# SIM808.net
KiCad netlist of a schematic drawn in Altium Designer
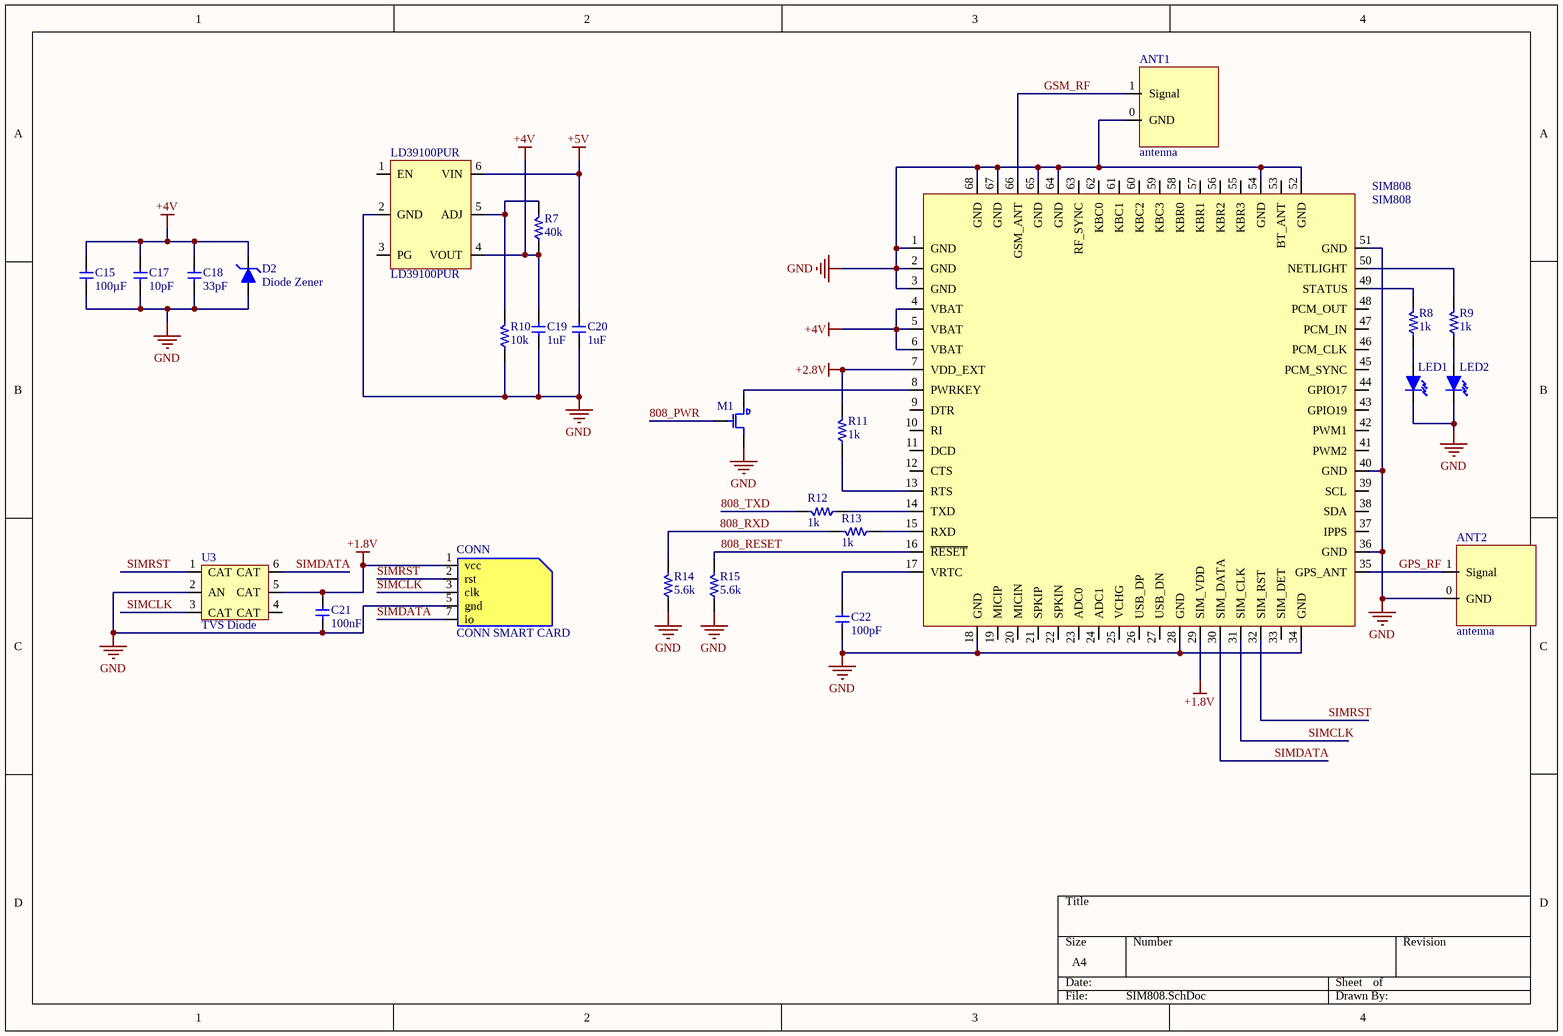
[diagram p0: SIM808.SchDoc]

(export (version "E")
  (design (tool "Eeschema 10.0.6"))
  (components
    (comp (ref "ANT1")
      (value "antenna")
      (footprint "uFL")
      (description "uFL SMT Antenna Connector")
      (fields (field (name "MFR") "adafruit"))
      (libsource (lib "uFLAntenna") (part "antenna"))
    )
    (comp (ref "ANT2")
      (value "antenna")
      (footprint "uFL")
      (description "uFL SMT Antenna Connector")
      (fields (field (name "MFR") "adafruit"))
      (libsource (lib "uFLAntenna") (part "antenna"))
    )
    (comp (ref "C15")
      (value "Cap Cer 100uF")
      (footprint "Cap 1210")
      (description "CAP CER 100UF 10V X5R 1210")
      (fields
        (field (name "MANUFACTURER") "Taiyo Yuden")
        (field (name "MANUFACTURER PART NUMBER") "LMK325ABJ107MM-P")
        (field (name "CAPACITANCE") "100µF")
      )
      (libsource (lib "SIM808") (part "LMK325ABJ107MM-P"))
    )
    (comp (ref "C17")
      (value "10pF")
      (footprint "0805")
      (description "Generic capacitor")
      (fields (field (name "Comment") "Generic Capacitor"))
      (libsource (lib "PowerCircuit") (part "Capacitor"))
    )
    (comp (ref "C18")
      (value "33pF")
      (footprint "0805")
      (description "Generic capacitor")
      (fields (field (name "Comment") "Generic Capacitor"))
      (libsource (lib "PowerCircuit") (part "Capacitor"))
    )
    (comp (ref "C19")
      (value "1uF")
      (footprint "0805")
      (description "Generic capacitor")
      (fields (field (name "Comment") "Generic Capacitor"))
      (libsource (lib "PowerCircuit") (part "Capacitor"))
    )
    (comp (ref "C20")
      (value "1uF")
      (footprint "0805")
      (description "Generic capacitor")
      (fields (field (name "Comment") "Generic Capacitor"))
      (libsource (lib "PowerCircuit") (part "Capacitor"))
    )
    (comp (ref "C21")
      (value "100nF")
      (footprint "0805")
      (description "Generic capacitor")
      (fields (field (name "Comment") "Generic Capacitor"))
      (libsource (lib "PowerCircuit") (part "Capacitor"))
    )
    (comp (ref "C22")
      (value "100pF")
      (footprint "0805")
      (description "Generic capacitor")
      (fields (field (name "Comment") "Generic Capacitor"))
      (libsource (lib "PowerCircuit") (part "Capacitor"))
    )
    (comp (ref "CONN")
      (value "CONN SMART CARD")
      (footprint "CONN SMART CARD")
      (fields
        (field (name "MANUFACTURER") "Wurth Electronics Inc")
        (field (name "MANUFACTURER PART NUMBER") "693022010811")
      )
      (libsource (lib "SIM808") (part "CONN SMART CARD"))
    )
    (comp (ref "D2")
      (value "Diode Zener")
      (footprint "Diode Zener")
      (description "DIODE ZENER 5.1V 500MW SOD123")
      (fields
        (field (name "MANUFACTURER") "ON Semiconductor")
        (field (name "MANUFACTURER PART NUMBER") "MMSZ5231BT1G")
      )
      (libsource (lib "SIM808") (part "MMSZ5231BT1G"))
    )
    (comp (ref "LD39100PUR")
      (value "LD39100PUR")
      (footprint "LD39100PUR")
      (description "Adjustable linear voltage regulator")
      (fields (field (name "MFR") "ST"))
      (libsource (lib "SIM808") (part "LD39100PUR"))
    )
    (comp (ref "LED1")
      (value "Led Red")
      (footprint "0805 LED")
      (description "LED RED CLEAR 0805 SMD")
      (fields
        (field (name "MANUFACTURER") "Lite-On Inc.")
        (field (name "MANUFACTURER PART NUMBER") "LTST-C171EKT")
      )
      (libsource (lib "SIM808") (part "LTST-C171EKT"))
    )
    (comp (ref "LED2")
      (value "Led Green")
      (footprint "0805 LED")
      (description "LED GREEN CLEAR 0805 SMD")
      (fields
        (field (name "MANUFACTURER") "Lite-On Inc.")
        (field (name "MANUFACTURER PART NUMBER") "LTST-C170GKT")
      )
      (libsource (lib "SIM808") (part "LTST-C170GKT"))
    )
    (comp (ref "M1")
      (value "N-CH Mosfet Switch")
      (footprint "SOT32-3")
      (description "MOSFET N-CH 20V 1.05A SOT23")
      (fields
        (field (name "MANUFACTURER") "NXP USA Inc.")
        (field (name "MANUFACTURER PART NUMBER") "BSH105,215")
      )
      (libsource (lib "SIM808") (part "BSH105,215"))
    )
    (comp (ref "R7")
      (value "40k")
      (footprint "0805")
      (description "Generic Resistor")
      (fields (field (name "Comment") "Resistor"))
      (libsource (lib "PowerCircuit") (part "Resistor"))
    )
    (comp (ref "R8")
      (value "1k")
      (footprint "0805")
      (description "Generic Resistor")
      (fields (field (name "Comment") "Resistor"))
      (libsource (lib "PowerCircuit") (part "Resistor"))
    )
    (comp (ref "R9")
      (value "1k")
      (footprint "0805")
      (description "Generic Resistor")
      (fields (field (name "Comment") "Resistor"))
      (libsource (lib "PowerCircuit") (part "Resistor"))
    )
    (comp (ref "R10")
      (value "10k")
      (footprint "0805")
      (description "Generic Resistor")
      (fields (field (name "Comment") "Resistor"))
      (libsource (lib "PowerCircuit") (part "Resistor"))
    )
    (comp (ref "R11")
      (value "1k")
      (footprint "0805")
      (description "Generic Resistor")
      (fields (field (name "Comment") "Resistor"))
      (libsource (lib "PowerCircuit") (part "Resistor"))
    )
    (comp (ref "R12")
      (value "1k")
      (footprint "0805")
      (description "Generic Resistor")
      (fields (field (name "Comment") "Resistor"))
      (libsource (lib "PowerCircuit") (part "Resistor"))
    )
    (comp (ref "R13")
      (value "1k")
      (footprint "0805")
      (description "Generic Resistor")
      (fields (field (name "Comment") "Resistor"))
      (libsource (lib "PowerCircuit") (part "Resistor"))
    )
    (comp (ref "R14")
      (value "5.6k")
      (footprint "0805")
      (description "Generic Resistor")
      (fields (field (name "Comment") "Resistor"))
      (libsource (lib "PowerCircuit") (part "Resistor"))
    )
    (comp (ref "R15")
      (value "5.6k")
      (footprint "0805")
      (description "Generic Resistor")
      (fields (field (name "Comment") "Resistor"))
      (libsource (lib "PowerCircuit") (part "Resistor"))
    )
    (comp (ref "SIM808")
      (value "SIM808")
      (footprint "SIM808")
      (description "SIM808 GSM + GPRS + GPS Cellular Module")
      (fields (field (name "MFR") "SimCom"))
      (libsource (lib "SIM808") (part "SIM808"))
    )
    (comp (ref "U3")
      (value "TVS Diode")
      (footprint "SMF05CT2G")
      (description "TVS DIODE 5VWM 12.5VC SOT363")
      (fields
        (field (name "MANUFACTURER") "ON Semiconductor")
        (field (name "MANUFACTURER PART NUMBER") "SMF05CT2G")
      )
      (libsource (lib "SIM808") (part "SMF05CT2G"))
    )
  )
  (nets
    (net (code "1") (name "+1.8V") (class "Default")
      (node (ref "C21") (pin "1") (pinfunction "1_1") (pintype "passive"))
      (node (ref "CONN") (pin "1") (pinfunction "vcc_1") (pintype "passive"))
      (node (ref "SIM808") (pin "29") (pinfunction "SIM_VDD_29") (pintype "passive"))
      (node (ref "U3") (pin "5") (pinfunction "CAT_5") (pintype "passive"))
    )
    (net (code "2") (name "+2.8V") (class "Default")
      (node (ref "R11") (pin "2") (pinfunction "2_2") (pintype "passive"))
      (node (ref "SIM808") (pin "7") (pinfunction "VDD_EXT_7") (pintype "passive"))
    )
    (net (code "3") (name "+4V") (class "Default")
      (node (ref "C15") (pin "1") (pinfunction "1_1") (pintype "passive"))
      (node (ref "C17") (pin "1") (pinfunction "1_1") (pintype "passive"))
      (node (ref "C18") (pin "1") (pinfunction "1_1") (pintype "passive"))
      (node (ref "C19") (pin "2") (pinfunction "2_2") (pintype "passive"))
      (node (ref "D2") (pin "1") (pinfunction "1_1") (pintype "passive"))
      (node (ref "LD39100PUR") (pin "4") (pinfunction "VOUT_4") (pintype "passive"))
      (node (ref "R7") (pin "1") (pinfunction "1_1") (pintype "passive"))
      (node (ref "SIM808") (pin "4") (pinfunction "VBAT_4") (pintype "passive"))
      (node (ref "SIM808") (pin "5") (pinfunction "VBAT_5") (pintype "passive"))
      (node (ref "SIM808") (pin "6") (pinfunction "VBAT_6") (pintype "passive"))
    )
    (net (code "4") (name "+5V") (class "Default")
      (node (ref "C20") (pin "1") (pinfunction "1_1") (pintype "passive"))
      (node (ref "LD39100PUR") (pin "6") (pinfunction "VIN_6") (pintype "passive"))
    )
    (net (code "5") (name "/808_PWR") (class "Default")
      (node (ref "M1") (pin "1") (pinfunction "G_1") (pintype "passive"))
    )
    (net (code "6") (name "/808_RESET") (class "Default")
      (node (ref "R15") (pin "2") (pinfunction "2_2") (pintype "passive"))
      (node (ref "SIM808") (pin "16") (pinfunction "~{RESET}_16") (pintype "passive"))
    )
    (net (code "7") (name "/808_RXD") (class "Default")
      (node (ref "R13") (pin "2") (pinfunction "2_2") (pintype "passive"))
      (node (ref "R14") (pin "2") (pinfunction "2_2") (pintype "passive"))
    )
    (net (code "8") (name "/808_TXD") (class "Default")
      (node (ref "R12") (pin "2") (pinfunction "2_2") (pintype "passive"))
    )
    (net (code "9") (name "/GPS_RF") (class "Default")
      (node (ref "ANT2") (pin "1") (pinfunction "Signal_1") (pintype "passive"))
      (node (ref "SIM808") (pin "35") (pinfunction "GPS_ANT_35") (pintype "passive"))
    )
    (net (code "10") (name "/GSM_RF") (class "Default")
      (node (ref "ANT1") (pin "1") (pinfunction "Signal_1") (pintype "passive"))
      (node (ref "SIM808") (pin "66") (pinfunction "GSM_ANT_66") (pintype "passive"))
    )
    (net (code "11") (name "/SIMCLK") (class "Default")
      (node (ref "CONN") (pin "3") (pinfunction "clk_3") (pintype "passive"))
      (node (ref "SIM808") (pin "31") (pinfunction "SIM_CLK_31") (pintype "passive"))
      (node (ref "U3") (pin "3") (pinfunction "CAT_3") (pintype "passive"))
    )
    (net (code "12") (name "/SIMDATA") (class "Default")
      (node (ref "CONN") (pin "7") (pinfunction "io_7") (pintype "passive"))
      (node (ref "SIM808") (pin "30") (pinfunction "SIM_DATA_30") (pintype "passive"))
      (node (ref "U3") (pin "6") (pinfunction "CAT_6") (pintype "passive"))
    )
    (net (code "13") (name "/SIMRST") (class "Default")
      (node (ref "CONN") (pin "2") (pinfunction "rst_2") (pintype "passive"))
      (node (ref "SIM808") (pin "32") (pinfunction "SIM_RST_32") (pintype "passive"))
      (node (ref "U3") (pin "1") (pinfunction "CAT_1") (pintype "passive"))
    )
    (net (code "14") (name "GND") (class "Default")
      (node (ref "ANT1") (pin "0") (pinfunction "GND_0") (pintype "passive"))
      (node (ref "ANT2") (pin "0") (pinfunction "GND_0") (pintype "passive"))
      (node (ref "C15") (pin "2") (pinfunction "2_2") (pintype "passive"))
      (node (ref "C17") (pin "2") (pinfunction "2_2") (pintype "passive"))
      (node (ref "C18") (pin "2") (pinfunction "2_2") (pintype "passive"))
      (node (ref "C19") (pin "1") (pinfunction "1_1") (pintype "passive"))
      (node (ref "C20") (pin "2") (pinfunction "2_2") (pintype "passive"))
      (node (ref "C21") (pin "2") (pinfunction "2_2") (pintype "passive"))
      (node (ref "C22") (pin "2") (pinfunction "2_2") (pintype "passive"))
      (node (ref "CONN") (pin "5") (pinfunction "gnd_5") (pintype "passive"))
      (node (ref "D2") (pin "2") (pinfunction "2_2") (pintype "passive"))
      (node (ref "LD39100PUR") (pin "2") (pinfunction "GND_2") (pintype "passive"))
      (node (ref "LED1") (pin "1") (pinfunction "1_1") (pintype "passive"))
      (node (ref "LED2") (pin "1") (pinfunction "1_1") (pintype "passive"))
      (node (ref "M1") (pin "2") (pinfunction "S_2") (pintype "passive"))
      (node (ref "R10") (pin "1") (pinfunction "1_1") (pintype "passive"))
      (node (ref "R14") (pin "1") (pinfunction "1_1") (pintype "passive"))
      (node (ref "R15") (pin "1") (pinfunction "1_1") (pintype "passive"))
      (node (ref "SIM808") (pin "1") (pinfunction "GND_1") (pintype "passive"))
      (node (ref "SIM808") (pin "18") (pinfunction "GND_18") (pintype "passive"))
      (node (ref "SIM808") (pin "2") (pinfunction "GND_2") (pintype "passive"))
      (node (ref "SIM808") (pin "28") (pinfunction "GND_28") (pintype "passive"))
      (node (ref "SIM808") (pin "3") (pinfunction "GND_3") (pintype "passive"))
      (node (ref "SIM808") (pin "34") (pinfunction "GND_34") (pintype "passive"))
      (node (ref "SIM808") (pin "36") (pinfunction "GND_36") (pintype "passive"))
      (node (ref "SIM808") (pin "40") (pinfunction "GND_40") (pintype "passive"))
      (node (ref "SIM808") (pin "51") (pinfunction "GND_51") (pintype "passive"))
      (node (ref "SIM808") (pin "52") (pinfunction "GND_52") (pintype "passive"))
      (node (ref "SIM808") (pin "54") (pinfunction "GND_54") (pintype "passive"))
      (node (ref "SIM808") (pin "64") (pinfunction "GND_64") (pintype "passive"))
      (node (ref "SIM808") (pin "65") (pinfunction "GND_65") (pintype "passive"))
      (node (ref "SIM808") (pin "67") (pinfunction "GND_67") (pintype "passive"))
      (node (ref "SIM808") (pin "68") (pinfunction "GND_68") (pintype "passive"))
      (node (ref "U3") (pin "2") (pinfunction "AN_2") (pintype "passive"))
    )
    (net (code "15") (name "Net-(LD39100PUR-ADJ)") (class "Default")
      (node (ref "LD39100PUR") (pin "5") (pinfunction "ADJ_5") (pintype "passive"))
      (node (ref "R10") (pin "2") (pinfunction "2_2") (pintype "passive"))
      (node (ref "R7") (pin "2") (pinfunction "2_2") (pintype "passive"))
    )
    (net (code "16") (name "Net-(LED1-Pad2)") (class "Default")
      (node (ref "LED1") (pin "2") (pinfunction "2_2") (pintype "passive"))
      (node (ref "R8") (pin "1") (pinfunction "1_1") (pintype "passive"))
    )
    (net (code "17") (name "Net-(LED2-Pad2)") (class "Default")
      (node (ref "LED2") (pin "2") (pinfunction "2_2") (pintype "passive"))
      (node (ref "R9") (pin "1") (pinfunction "1_1") (pintype "passive"))
    )
    (net (code "18") (name "Net-(M1-D)") (class "Default")
      (node (ref "M1") (pin "3") (pinfunction "D_3") (pintype "passive"))
      (node (ref "SIM808") (pin "8") (pinfunction "PWRKEY_8") (pintype "passive"))
    )
    (net (code "19") (name "Net-(SIM808-NETLIGHT)") (class "Default")
      (node (ref "R9") (pin "2") (pinfunction "2_2") (pintype "passive"))
      (node (ref "SIM808") (pin "50") (pinfunction "NETLIGHT_50") (pintype "passive"))
    )
    (net (code "20") (name "Net-(SIM808-RTS)") (class "Default")
      (node (ref "R11") (pin "1") (pinfunction "1_1") (pintype "passive"))
      (node (ref "SIM808") (pin "13") (pinfunction "RTS_13") (pintype "passive"))
    )
    (net (code "21") (name "Net-(SIM808-RXD)") (class "Default")
      (node (ref "R13") (pin "1") (pinfunction "1_1") (pintype "passive"))
      (node (ref "SIM808") (pin "15") (pinfunction "RXD_15") (pintype "passive"))
    )
    (net (code "22") (name "Net-(SIM808-STATUS)") (class "Default")
      (node (ref "R8") (pin "2") (pinfunction "2_2") (pintype "passive"))
      (node (ref "SIM808") (pin "49") (pinfunction "STATUS_49") (pintype "passive"))
    )
    (net (code "23") (name "Net-(SIM808-TXD)") (class "Default")
      (node (ref "R12") (pin "1") (pinfunction "1_1") (pintype "passive"))
      (node (ref "SIM808") (pin "14") (pinfunction "TXD_14") (pintype "passive"))
    )
    (net (code "24") (name "Net-(SIM808-VRTC)") (class "Default")
      (node (ref "C22") (pin "1") (pinfunction "1_1") (pintype "passive"))
      (node (ref "SIM808") (pin "17") (pinfunction "VRTC_17") (pintype "passive"))
    )
    (net (code "25") (name "unconnected-(LD39100PUR-EN-Pad1)") (class "Default")
      (node (ref "LD39100PUR") (pin "1") (pinfunction "EN_1") (pintype "passive"))
    )
    (net (code "26") (name "unconnected-(LD39100PUR-PG-Pad3)") (class "Default")
      (node (ref "LD39100PUR") (pin "3") (pinfunction "PG_3") (pintype "passive"))
    )
    (net (code "27") (name "unconnected-(SIM808-ADC0-Pad23)") (class "Default")
      (node (ref "SIM808") (pin "23") (pinfunction "ADC0_23") (pintype "passive"))
    )
    (net (code "28") (name "unconnected-(SIM808-ADC1-Pad24)") (class "Default")
      (node (ref "SIM808") (pin "24") (pinfunction "ADC1_24") (pintype "passive"))
    )
    (net (code "29") (name "unconnected-(SIM808-BT_ANT-Pad53)") (class "Default")
      (node (ref "SIM808") (pin "53") (pinfunction "BT_ANT_53") (pintype "passive"))
    )
    (net (code "30") (name "unconnected-(SIM808-CTS-Pad12)") (class "Default")
      (node (ref "SIM808") (pin "12") (pinfunction "CTS_12") (pintype "passive"))
    )
    (net (code "31") (name "unconnected-(SIM808-DCD-Pad11)") (class "Default")
      (node (ref "SIM808") (pin "11") (pinfunction "DCD_11") (pintype "passive"))
    )
    (net (code "32") (name "unconnected-(SIM808-DTR-Pad9)") (class "Default")
      (node (ref "SIM808") (pin "9") (pinfunction "DTR_9") (pintype "passive"))
    )
    (net (code "33") (name "unconnected-(SIM808-GPIO17-Pad44)") (class "Default")
      (node (ref "SIM808") (pin "44") (pinfunction "GPIO17_44") (pintype "passive"))
    )
    (net (code "34") (name "unconnected-(SIM808-GPIO19-Pad43)") (class "Default")
      (node (ref "SIM808") (pin "43") (pinfunction "GPIO19_43") (pintype "passive"))
    )
    (net (code "35") (name "unconnected-(SIM808-IPPS-Pad37)") (class "Default")
      (node (ref "SIM808") (pin "37") (pinfunction "IPPS_37") (pintype "passive"))
    )
    (net (code "36") (name "unconnected-(SIM808-KBC0-Pad62)") (class "Default")
      (node (ref "SIM808") (pin "62") (pinfunction "KBC0_62") (pintype "passive"))
    )
    (net (code "37") (name "unconnected-(SIM808-KBC1-Pad61)") (class "Default")
      (node (ref "SIM808") (pin "61") (pinfunction "KBC1_61") (pintype "passive"))
    )
    (net (code "38") (name "unconnected-(SIM808-KBC2-Pad60)") (class "Default")
      (node (ref "SIM808") (pin "60") (pinfunction "KBC2_60") (pintype "passive"))
    )
    (net (code "39") (name "unconnected-(SIM808-KBC3-Pad59)") (class "Default")
      (node (ref "SIM808") (pin "59") (pinfunction "KBC3_59") (pintype "passive"))
    )
    (net (code "40") (name "unconnected-(SIM808-KBR0-Pad58)") (class "Default")
      (node (ref "SIM808") (pin "58") (pinfunction "KBR0_58") (pintype "passive"))
    )
    (net (code "41") (name "unconnected-(SIM808-KBR1-Pad57)") (class "Default")
      (node (ref "SIM808") (pin "57") (pinfunction "KBR1_57") (pintype "passive"))
    )
    (net (code "42") (name "unconnected-(SIM808-KBR2-Pad56)") (class "Default")
      (node (ref "SIM808") (pin "56") (pinfunction "KBR2_56") (pintype "passive"))
    )
    (net (code "43") (name "unconnected-(SIM808-KBR3-Pad55)") (class "Default")
      (node (ref "SIM808") (pin "55") (pinfunction "KBR3_55") (pintype "passive"))
    )
    (net (code "44") (name "unconnected-(SIM808-MICIN-Pad20)") (class "Default")
      (node (ref "SIM808") (pin "20") (pinfunction "MICIN_20") (pintype "passive"))
    )
    (net (code "45") (name "unconnected-(SIM808-MICIP-Pad19)") (class "Default")
      (node (ref "SIM808") (pin "19") (pinfunction "MICIP_19") (pintype "passive"))
    )
    (net (code "46") (name "unconnected-(SIM808-PCM_CLK-Pad46)") (class "Default")
      (node (ref "SIM808") (pin "46") (pinfunction "PCM_CLK_46") (pintype "passive"))
    )
    (net (code "47") (name "unconnected-(SIM808-PCM_IN-Pad47)") (class "Default")
      (node (ref "SIM808") (pin "47") (pinfunction "PCM_IN_47") (pintype "passive"))
    )
    (net (code "48") (name "unconnected-(SIM808-PCM_OUT-Pad48)") (class "Default")
      (node (ref "SIM808") (pin "48") (pinfunction "PCM_OUT_48") (pintype "passive"))
    )
    (net (code "49") (name "unconnected-(SIM808-PCM_SYNC-Pad45)") (class "Default")
      (node (ref "SIM808") (pin "45") (pinfunction "PCM_SYNC_45") (pintype "passive"))
    )
    (net (code "50") (name "unconnected-(SIM808-PWM1-Pad42)") (class "Default")
      (node (ref "SIM808") (pin "42") (pinfunction "PWM1_42") (pintype "passive"))
    )
    (net (code "51") (name "unconnected-(SIM808-PWM2-Pad41)") (class "Default")
      (node (ref "SIM808") (pin "41") (pinfunction "PWM2_41") (pintype "passive"))
    )
    (net (code "52") (name "unconnected-(SIM808-RF_SYNC-Pad63)") (class "Default")
      (node (ref "SIM808") (pin "63") (pinfunction "RF_SYNC_63") (pintype "passive"))
    )
    (net (code "53") (name "unconnected-(SIM808-RI-Pad10)") (class "Default")
      (node (ref "SIM808") (pin "10") (pinfunction "RI_10") (pintype "passive"))
    )
    (net (code "54") (name "unconnected-(SIM808-SCL-Pad39)") (class "Default")
      (node (ref "SIM808") (pin "39") (pinfunction "SCL_39") (pintype "passive"))
    )
    (net (code "55") (name "unconnected-(SIM808-SDA-Pad38)") (class "Default")
      (node (ref "SIM808") (pin "38") (pinfunction "SDA_38") (pintype "passive"))
    )
    (net (code "56") (name "unconnected-(SIM808-SIM_DET-Pad33)") (class "Default")
      (node (ref "SIM808") (pin "33") (pinfunction "SIM_DET_33") (pintype "passive"))
    )
    (net (code "57") (name "unconnected-(SIM808-SPKIN-Pad22)") (class "Default")
      (node (ref "SIM808") (pin "22") (pinfunction "SPKIN_22") (pintype "passive"))
    )
    (net (code "58") (name "unconnected-(SIM808-SPKIP-Pad21)") (class "Default")
      (node (ref "SIM808") (pin "21") (pinfunction "SPKIP_21") (pintype "passive"))
    )
    (net (code "59") (name "unconnected-(SIM808-USB_DN-Pad27)") (class "Default")
      (node (ref "SIM808") (pin "27") (pinfunction "USB_DN_27") (pintype "passive"))
    )
    (net (code "60") (name "unconnected-(SIM808-USB_DP-Pad26)") (class "Default")
      (node (ref "SIM808") (pin "26") (pinfunction "USB_DP_26") (pintype "passive"))
    )
    (net (code "61") (name "unconnected-(SIM808-VCHG-Pad25)") (class "Default")
      (node (ref "SIM808") (pin "25") (pinfunction "VCHG_25") (pintype "passive"))
    )
    (net (code "62") (name "unconnected-(U3-CAT-Pad4)") (class "Default")
      (node (ref "U3") (pin "4") (pinfunction "CAT_4") (pintype "passive"))
    )
  )
)
